# ESP8266_Stepper_Driver_easyeda.net
KiCad netlist of a schematic drawn in EasyEDA
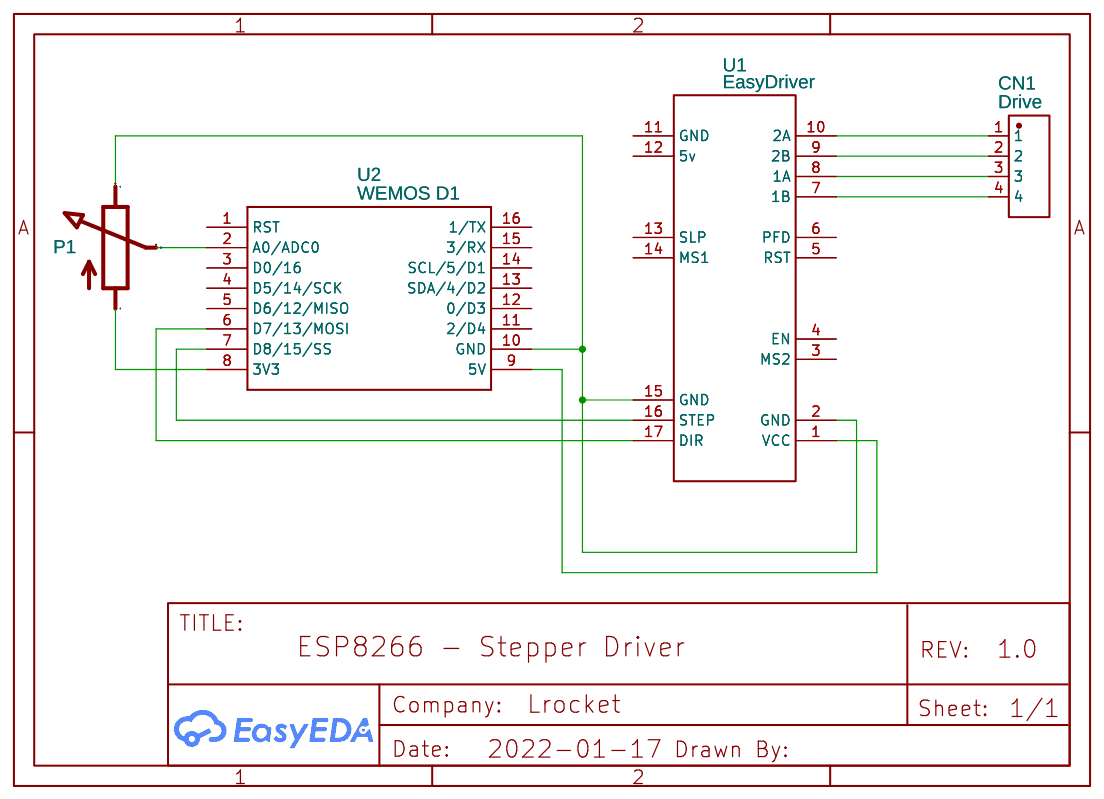
[diagram p0: schematic sheet]

(export (version "E")
  (design (tool "Eeschema 10.0.6"))
  (components
    (comp (ref "CN1")
      (value "Drive")
      (fields
        (field (name "BOM_Manufacturer Part") "FLY4-Header4")
        (field (name "BOM_Supplier Part") "C9900006105")
      )
      (libsource (lib "") (part "FLY4-HEADER4"))
    )
    (comp (ref "P1") (value "Poti") (libsource (lib "") (part "POTI_MONO_XL")))
    (comp (ref "U1") (value "EasyDriver") (libsource (lib "") (part "EasyDriver")))
    (comp (ref "U2") (value "WEMOS D1") (libsource (lib "") (part "WEMOS D1")))
  )
  (nets
    (net (code "1") (name "Net-(P1-A)") (class "Default")
      (node (ref "P1") (pin "1") (pinfunction "A_1") (pintype "unspecified"))
      (node (ref "U2") (pin "8") (pinfunction "3V3_8") (pintype "unspecified"))
    )
    (net (code "2") (name "Net-(P1-E)") (class "Default")
      (node (ref "P1") (pin "2") (pinfunction "E_2") (pintype "unspecified"))
      (node (ref "U1") (pin "15") (pinfunction "GND_15") (pintype "unspecified"))
      (node (ref "U1") (pin "2") (pinfunction "GND_2") (pintype "unspecified"))
      (node (ref "U2") (pin "10") (pinfunction "GND_10") (pintype "unspecified"))
    )
    (net (code "3") (name "Net-(P1-S)") (class "Default")
      (node (ref "P1") (pin "3") (pinfunction "S_3") (pintype "unspecified"))
      (node (ref "U2") (pin "2") (pinfunction "A0/ADC0_2") (pintype "unspecified"))
    )
    (net (code "4") (name "Net-(U1-1A)") (class "Default")
      (node (ref "CN1") (pin "3") (pinfunction "3_3") (pintype "unspecified"))
      (node (ref "U1") (pin "8") (pinfunction "1A_8") (pintype "unspecified"))
    )
    (net (code "5") (name "Net-(U1-1B)") (class "Default")
      (node (ref "CN1") (pin "4") (pinfunction "4_4") (pintype "unspecified"))
      (node (ref "U1") (pin "7") (pinfunction "1B_7") (pintype "unspecified"))
    )
    (net (code "6") (name "Net-(U1-2A)") (class "Default")
      (node (ref "CN1") (pin "1") (pinfunction "1_1") (pintype "unspecified"))
      (node (ref "U1") (pin "10") (pinfunction "2A_10") (pintype "unspecified"))
    )
    (net (code "7") (name "Net-(U1-2B)") (class "Default")
      (node (ref "CN1") (pin "2") (pinfunction "2_2") (pintype "unspecified"))
      (node (ref "U1") (pin "9") (pinfunction "2B_9") (pintype "unspecified"))
    )
    (net (code "8") (name "Net-(U1-DIR)") (class "Default")
      (node (ref "U1") (pin "17") (pinfunction "DIR_17") (pintype "unspecified"))
      (node (ref "U2") (pin "6") (pinfunction "D7/13/MOSI_6") (pintype "unspecified"))
    )
    (net (code "9") (name "Net-(U1-STEP)") (class "Default")
      (node (ref "U1") (pin "16") (pinfunction "STEP_16") (pintype "unspecified"))
      (node (ref "U2") (pin "7") (pinfunction "D8/15/SS_7") (pintype "unspecified"))
    )
    (net (code "10") (name "Net-(U1-VCC)") (class "Default")
      (node (ref "U1") (pin "1") (pinfunction "VCC_1") (pintype "unspecified"))
      (node (ref "U2") (pin "9") (pinfunction "5V_9") (pintype "unspecified"))
    )
    (net (code "11") (name "unconnected-(U1-5v-Pad12)") (class "Default")
      (node (ref "U1") (pin "12") (pinfunction "5v_12") (pintype "unspecified"))
    )
    (net (code "12") (name "unconnected-(U1-EN-Pad4)") (class "Default")
      (node (ref "U1") (pin "4") (pinfunction "EN_4") (pintype "unspecified"))
    )
    (net (code "13") (name "unconnected-(U1-GND-Pad11)") (class "Default")
      (node (ref "U1") (pin "11") (pinfunction "GND_11") (pintype "unspecified"))
    )
    (net (code "14") (name "unconnected-(U1-MS1-Pad14)") (class "Default")
      (node (ref "U1") (pin "14") (pinfunction "MS1_14") (pintype "unspecified"))
    )
    (net (code "15") (name "unconnected-(U1-MS2-Pad3)") (class "Default")
      (node (ref "U1") (pin "3") (pinfunction "MS2_3") (pintype "unspecified"))
    )
    (net (code "16") (name "unconnected-(U1-PFD-Pad6)") (class "Default")
      (node (ref "U1") (pin "6") (pinfunction "PFD_6") (pintype "unspecified"))
    )
    (net (code "17") (name "unconnected-(U1-RST-Pad5)") (class "Default")
      (node (ref "U1") (pin "5") (pinfunction "RST_5") (pintype "unspecified"))
    )
    (net (code "18") (name "unconnected-(U1-SLP-Pad13)") (class "Default")
      (node (ref "U1") (pin "13") (pinfunction "SLP_13") (pintype "unspecified"))
    )
    (net (code "19") (name "unconnected-(U2-0{slash}D3-Pad12)") (class "Default")
      (node (ref "U2") (pin "12") (pinfunction "0/D3_12") (pintype "unspecified"))
    )
    (net (code "20") (name "unconnected-(U2-1{slash}TX-Pad16)") (class "Default")
      (node (ref "U2") (pin "16") (pinfunction "1/TX_16") (pintype "unspecified"))
    )
    (net (code "21") (name "unconnected-(U2-2{slash}D4-Pad11)") (class "Default")
      (node (ref "U2") (pin "11") (pinfunction "2/D4_11") (pintype "unspecified"))
    )
    (net (code "22") (name "unconnected-(U2-3{slash}RX-Pad15)") (class "Default")
      (node (ref "U2") (pin "15") (pinfunction "3/RX_15") (pintype "unspecified"))
    )
    (net (code "23") (name "unconnected-(U2-D0{slash}16-Pad3)") (class "Default")
      (node (ref "U2") (pin "3") (pinfunction "D0/16_3") (pintype "unspecified"))
    )
    (net (code "24") (name "unconnected-(U2-D5{slash}14{slash}SCK-Pad4)") (class "Default")
      (node (ref "U2") (pin "4") (pinfunction "D5/14/SCK_4") (pintype "unspecified"))
    )
    (net (code "25") (name "unconnected-(U2-D6{slash}12{slash}MISO-Pad5)") (class "Default")
      (node (ref "U2") (pin "5") (pinfunction "D6/12/MISO_5") (pintype "unspecified"))
    )
    (net (code "26") (name "unconnected-(U2-RST-Pad1)") (class "Default")
      (node (ref "U2") (pin "1") (pinfunction "RST_1") (pintype "unspecified"))
    )
    (net (code "27") (name "unconnected-(U2-SCL{slash}5{slash}D1-Pad14)") (class "Default")
      (node (ref "U2") (pin "14") (pinfunction "SCL/5/D1_14") (pintype "unspecified"))
    )
    (net (code "28") (name "unconnected-(U2-SDA{slash}4{slash}D2-Pad13)") (class "Default")
      (node (ref "U2") (pin "13") (pinfunction "SDA/4/D2_13") (pintype "unspecified"))
    )
  )
)
